# Arduino_Breakout.net
KiCad netlist of a schematic drawn in Altium Designer
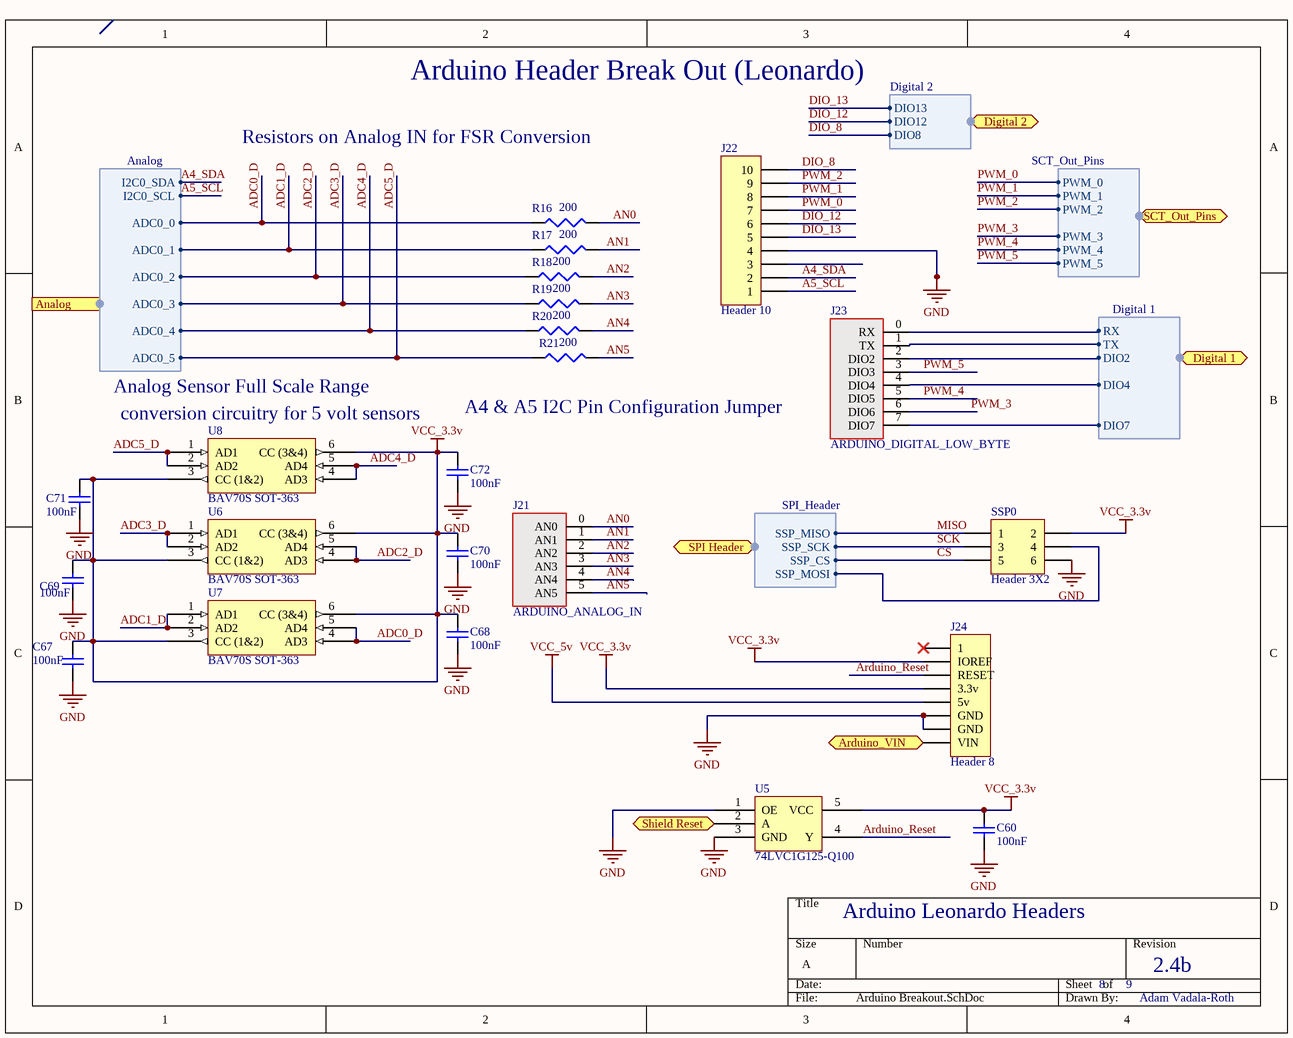
[diagram p0: Arduino Breakout.SchDoc]

(export (version "E")
  (design (tool "Eeschema 10.0.6"))
  (components
    (comp (ref "C60")
      (value "100nF")
      (footprint "1608[0603]")
      (description "Capacitor (Semiconductor SIM Model)")
      (fields (field (name "Comment") "Cap Semi") (field (name "PUBLISHER") "Altium Limited"))
      (libsource (lib "Miscellaneous Devices") (part "Cap Semi"))
    )
    (comp (ref "C67")
      (value "100nF")
      (footprint "1608[0603]")
      (description "Capacitor (Semiconductor SIM Model)")
      (fields (field (name "Comment") "Cap Semi") (field (name "PUBLISHER") "Altium Limited"))
      (libsource (lib "Miscellaneous Devices") (part "Cap Semi"))
    )
    (comp (ref "C68")
      (value "100nF")
      (footprint "1608[0603]")
      (description "Capacitor (Semiconductor SIM Model)")
      (fields (field (name "Comment") "Cap Semi") (field (name "PUBLISHER") "Altium Limited"))
      (libsource (lib "Miscellaneous Devices") (part "Cap Semi"))
    )
    (comp (ref "C69")
      (value "100nF")
      (footprint "1608[0603]")
      (description "Capacitor (Semiconductor SIM Model)")
      (fields (field (name "Comment") "Cap Semi") (field (name "PUBLISHER") "Altium Limited"))
      (libsource (lib "Miscellaneous Devices") (part "Cap Semi"))
    )
    (comp (ref "C70")
      (value "100nF")
      (footprint "1608[0603]")
      (description "Capacitor (Semiconductor SIM Model)")
      (fields (field (name "Comment") "Cap Semi") (field (name "PUBLISHER") "Altium Limited"))
      (libsource (lib "Miscellaneous Devices") (part "Cap Semi"))
    )
    (comp (ref "C71")
      (value "100nF")
      (footprint "1608[0603]")
      (description "Capacitor (Semiconductor SIM Model)")
      (fields (field (name "Comment") "Cap Semi") (field (name "PUBLISHER") "Altium Limited"))
      (libsource (lib "Miscellaneous Devices") (part "Cap Semi"))
    )
    (comp (ref "C72")
      (value "100nF")
      (footprint "1608[0603]")
      (description "Capacitor (Semiconductor SIM Model)")
      (fields (field (name "Comment") "Cap Semi") (field (name "PUBLISHER") "Altium Limited"))
      (libsource (lib "Miscellaneous Devices") (part "Cap Semi"))
    )
    (comp (ref "J21")
      (value "ARDUINO_ANALOG_IN")
      (footprint "HDR1X6")
      (description "6-pin socket")
      (libsource (lib "Rascal") (part "ARDUINO_ANALOG_IN"))
    )
    (comp (ref "J22")
      (value "Header 10")
      (footprint "HDR1X10")
      (description "Header, 10-Pin")
      (fields (field (name "PUBLISHER") "Altium Limited"))
      (libsource (lib "Miscellaneous Connectors") (part "Header 10"))
    )
    (comp (ref "J23")
      (value "ARDUINO_DIGITAL_LOW_BYTE")
      (footprint "HDR1X8")
      (description "8-pin socket")
      (libsource (lib "Rascal") (part "ARDUINO_DIGITAL_LOW_BYTE"))
    )
    (comp (ref "J24")
      (value "Header 8")
      (footprint "HDR1X8")
      (description "Header, 8-Pin")
      (fields (field (name "PUBLISHER") "Altium Limited"))
      (libsource (lib "Miscellaneous Connectors") (part "Header 8"))
    )
    (comp (ref "R16")
      (value "200")
      (footprint "J1-0603")
      (description "Resistor")
      (fields (field (name "Comment") "Res3") (field (name "PUBLISHER") "Altium Limited"))
      (libsource (lib "Miscellaneous Devices") (part "Res3"))
    )
    (comp (ref "R17")
      (value "200")
      (footprint "J1-0603")
      (description "Resistor")
      (fields (field (name "Comment") "Res3") (field (name "PUBLISHER") "Altium Limited"))
      (libsource (lib "Miscellaneous Devices") (part "Res3"))
    )
    (comp (ref "R18")
      (value "200")
      (footprint "J1-0603")
      (description "Resistor")
      (fields (field (name "Comment") "Res3") (field (name "PUBLISHER") "Altium Limited"))
      (libsource (lib "Miscellaneous Devices") (part "Res3"))
    )
    (comp (ref "R19")
      (value "200")
      (footprint "J1-0603")
      (description "Resistor")
      (fields (field (name "Comment") "Res3") (field (name "PUBLISHER") "Altium Limited"))
      (libsource (lib "Miscellaneous Devices") (part "Res3"))
    )
    (comp (ref "R20")
      (value "200")
      (footprint "J1-0603")
      (description "Resistor")
      (fields (field (name "Comment") "Res3") (field (name "PUBLISHER") "Altium Limited"))
      (libsource (lib "Miscellaneous Devices") (part "Res3"))
    )
    (comp (ref "R21")
      (value "200")
      (footprint "J1-0603")
      (description "Resistor")
      (fields (field (name "Comment") "Res3") (field (name "PUBLISHER") "Altium Limited"))
      (libsource (lib "Miscellaneous Devices") (part "Res3"))
    )
    (comp (ref "SSP0")
      (value "Header 3X2")
      (footprint "HDR2X3")
      (description "Header, 3-Pin, Dual row")
      (fields (field (name "PUBLISHER") "Altium Limited"))
      (libsource (lib "Miscellaneous Connectors") (part "Header 3X2"))
    )
    (comp (ref "U5")
      (value "74LVC1G125-Q100")
      (footprint "74LVC1G125-Q100")
      (libsource (lib "AHD Part Library") (part "74LVC1G125-Q100"))
    )
    (comp (ref "U6")
      (value "BAV70S SOT-363")
      (footprint "BAV70S_SOT363")
      (libsource (lib "AHD Part Library") (part "BAV70S SOT-363"))
    )
    (comp (ref "U7")
      (value "BAV70S SOT-363")
      (footprint "BAV70S_SOT363")
      (libsource (lib "AHD Part Library") (part "BAV70S SOT-363"))
    )
    (comp (ref "U8")
      (value "BAV70S SOT-363")
      (footprint "BAV70S_SOT363")
      (libsource (lib "AHD Part Library") (part "BAV70S SOT-363"))
    )
  )
  (nets
    (net (code "7") (name "/A4_SDA") (class "Default")
      (node (ref "J22") (pin "2") (pinfunction "2_2") (pintype "passive"))
    )
    (net (code "8") (name "/A5_SCL") (class "Default")
      (node (ref "J22") (pin "1") (pinfunction "1_1") (pintype "passive"))
    )
    (net (code "9") (name "/ADC0_D") (class "Default")
      (node (ref "R16") (pin "1") (pinfunction "1_1") (pintype "passive"))
      (node (ref "U7") (pin "4") (pinfunction "AD3_4") (pintype "input"))
      (node (ref "U7") (pin "5") (pinfunction "AD4_5") (pintype "input"))
    )
    (net (code "10") (name "/ADC1_D") (class "Default")
      (node (ref "R17") (pin "1") (pinfunction "1_1") (pintype "passive"))
      (node (ref "U7") (pin "1") (pinfunction "AD1_1") (pintype "input"))
      (node (ref "U7") (pin "2") (pinfunction "AD2_2") (pintype "input"))
    )
    (net (code "11") (name "/ADC2_D") (class "Default")
      (node (ref "R18") (pin "1") (pinfunction "1_1") (pintype "passive"))
      (node (ref "U6") (pin "4") (pinfunction "AD3_4") (pintype "input"))
      (node (ref "U6") (pin "5") (pinfunction "AD4_5") (pintype "input"))
    )
    (net (code "12") (name "/ADC3_D") (class "Default")
      (node (ref "R19") (pin "1") (pinfunction "1_1") (pintype "passive"))
      (node (ref "U6") (pin "1") (pinfunction "AD1_1") (pintype "input"))
      (node (ref "U6") (pin "2") (pinfunction "AD2_2") (pintype "input"))
    )
    (net (code "13") (name "/ADC4_D") (class "Default")
      (node (ref "R20") (pin "1") (pinfunction "1_1") (pintype "passive"))
      (node (ref "U8") (pin "4") (pinfunction "AD3_4") (pintype "input"))
      (node (ref "U8") (pin "5") (pinfunction "AD4_5") (pintype "input"))
    )
    (net (code "14") (name "/ADC5_D") (class "Default")
      (node (ref "R21") (pin "1") (pinfunction "1_1") (pintype "passive"))
      (node (ref "U8") (pin "1") (pinfunction "AD1_1") (pintype "input"))
      (node (ref "U8") (pin "2") (pinfunction "AD2_2") (pintype "input"))
    )
    (net (code "15") (name "/AN0") (class "Default")
      (node (ref "J21") (pin "0") (pinfunction "AN0_0") (pintype "passive"))
      (node (ref "R16") (pin "2") (pinfunction "2_2") (pintype "passive"))
    )
    (net (code "16") (name "/AN1") (class "Default")
      (node (ref "J21") (pin "1") (pinfunction "AN1_1") (pintype "passive"))
      (node (ref "R17") (pin "2") (pinfunction "2_2") (pintype "passive"))
    )
    (net (code "17") (name "/AN2") (class "Default")
      (node (ref "J21") (pin "2") (pinfunction "AN2_2") (pintype "passive"))
      (node (ref "R18") (pin "2") (pinfunction "2_2") (pintype "passive"))
    )
    (net (code "18") (name "/AN3") (class "Default")
      (node (ref "J21") (pin "3") (pinfunction "AN3_3") (pintype "passive"))
      (node (ref "R19") (pin "2") (pinfunction "2_2") (pintype "passive"))
    )
    (net (code "19") (name "/AN4") (class "Default")
      (node (ref "J21") (pin "4") (pinfunction "AN4_4") (pintype "passive"))
      (node (ref "R20") (pin "2") (pinfunction "2_2") (pintype "passive"))
    )
    (net (code "20") (name "/AN5") (class "Default")
      (node (ref "J21") (pin "5") (pinfunction "AN5_5") (pintype "passive"))
      (node (ref "R21") (pin "2") (pinfunction "2_2") (pintype "passive"))
    )
    (net (code "21") (name "/Arduino_Reset") (class "Default")
      (node (ref "J24") (pin "3") (pinfunction "RESET_3") (pintype "passive"))
      (node (ref "U5") (pin "4") (pinfunction "Y_4") (pintype "passive"))
    )
    (net (code "22") (name "/Arduino_VIN") (class "Default")
      (node (ref "J24") (pin "8") (pinfunction "VIN_8") (pintype "passive"))
    )
    (net (code "23") (name "/CS") (class "Default")
      (node (ref "SSP0") (pin "5") (pinfunction "5_5") (pintype "passive"))
    )
    (net (code "24") (name "/DIO2") (class "Default")
      (node (ref "J23") (pin "2") (pinfunction "DIO2_2") (pintype "passive"))
    )
    (net (code "25") (name "/DIO4") (class "Default")
      (node (ref "J23") (pin "4") (pinfunction "DIO4_4") (pintype "passive"))
    )
    (net (code "26") (name "/DIO7") (class "Default")
      (node (ref "J23") (pin "7") (pinfunction "DIO7_7") (pintype "passive"))
    )
    (net (code "27") (name "/DIO_8") (class "Default")
      (node (ref "J22") (pin "10") (pinfunction "10_10") (pintype "passive"))
    )
    (net (code "28") (name "/DIO_12") (class "Default")
      (node (ref "J22") (pin "6") (pinfunction "6_6") (pintype "passive"))
    )
    (net (code "29") (name "/DIO_13") (class "Default")
      (node (ref "J22") (pin "5") (pinfunction "5_5") (pintype "passive"))
    )
    (net (code "30") (name "/MISO") (class "Default")
      (node (ref "SSP0") (pin "1") (pinfunction "1_1") (pintype "passive"))
    )
    (net (code "31") (name "/PWM_0") (class "Default")
      (node (ref "J22") (pin "7") (pinfunction "7_7") (pintype "passive"))
    )
    (net (code "32") (name "/PWM_1") (class "Default")
      (node (ref "J22") (pin "8") (pinfunction "8_8") (pintype "passive"))
    )
    (net (code "33") (name "/PWM_2") (class "Default")
      (node (ref "J22") (pin "9") (pinfunction "9_9") (pintype "passive"))
    )
    (net (code "34") (name "/PWM_3") (class "Default")
      (node (ref "J23") (pin "6") (pinfunction "DIO6_6") (pintype "passive"))
    )
    (net (code "35") (name "/PWM_4") (class "Default")
      (node (ref "J23") (pin "5") (pinfunction "DIO5_5") (pintype "passive"))
    )
    (net (code "36") (name "/PWM_5") (class "Default")
      (node (ref "J23") (pin "3") (pinfunction "DIO3_3") (pintype "passive"))
    )
    (net (code "37") (name "/RX") (class "Default")
      (node (ref "J23") (pin "0") (pinfunction "RX_0") (pintype "passive"))
    )
    (net (code "38") (name "/SCK") (class "Default")
      (node (ref "SSP0") (pin "3") (pinfunction "3_3") (pintype "passive"))
    )
    (net (code "39") (name "/SSP_MOSI") (class "Default")
      (node (ref "SSP0") (pin "4") (pinfunction "4_4") (pintype "passive"))
    )
    (net (code "40") (name "/Shield Reset") (class "Default")
      (node (ref "U5") (pin "2") (pinfunction "A_2") (pintype "passive"))
    )
    (net (code "41") (name "/TX") (class "Default")
      (node (ref "J23") (pin "1") (pinfunction "TX_1") (pintype "passive"))
    )
    (net (code "47") (name "GND") (class "Default")
      (node (ref "C60") (pin "2") (pinfunction "2_2") (pintype "passive"))
      (node (ref "C67") (pin "2") (pinfunction "2_2") (pintype "passive"))
      (node (ref "C68") (pin "2") (pinfunction "2_2") (pintype "passive"))
      (node (ref "C69") (pin "2") (pinfunction "2_2") (pintype "passive"))
      (node (ref "C70") (pin "2") (pinfunction "2_2") (pintype "passive"))
      (node (ref "C71") (pin "2") (pinfunction "2_2") (pintype "passive"))
      (node (ref "C72") (pin "2") (pinfunction "2_2") (pintype "passive"))
      (node (ref "J22") (pin "4") (pinfunction "4_4") (pintype "passive"))
      (node (ref "J24") (pin "6") (pinfunction "GND_6") (pintype "passive"))
      (node (ref "J24") (pin "7") (pinfunction "GND_7") (pintype "passive"))
      (node (ref "SSP0") (pin "6") (pinfunction "6_6") (pintype "passive"))
      (node (ref "U5") (pin "1") (pinfunction "OE_1") (pintype "passive"))
      (node (ref "U5") (pin "3") (pinfunction "GND_3") (pintype "passive"))
    )
    (net (code "48") (name "VCC_3.3v") (class "Default")
      (node (ref "C60") (pin "1") (pinfunction "1_1") (pintype "passive"))
      (node (ref "C67") (pin "1") (pinfunction "1_1") (pintype "passive"))
      (node (ref "C68") (pin "1") (pinfunction "1_1") (pintype "passive"))
      (node (ref "C69") (pin "1") (pinfunction "1_1") (pintype "passive"))
      (node (ref "C70") (pin "1") (pinfunction "1_1") (pintype "passive"))
      (node (ref "C71") (pin "1") (pinfunction "1_1") (pintype "passive"))
      (node (ref "C72") (pin "1") (pinfunction "1_1") (pintype "passive"))
      (node (ref "J24") (pin "2") (pinfunction "IOREF_2") (pintype "passive"))
      (node (ref "J24") (pin "4") (pinfunction "3.3v_4") (pintype "passive"))
      (node (ref "SSP0") (pin "2") (pinfunction "2_2") (pintype "passive"))
      (node (ref "U5") (pin "5") (pinfunction "VCC_5") (pintype "passive"))
      (node (ref "U6") (pin "3") (pinfunction "CC_(1&2)_3") (pintype "output"))
      (node (ref "U6") (pin "6") (pinfunction "CC_(3&4)_6") (pintype "output"))
      (node (ref "U7") (pin "3") (pinfunction "CC_(1&2)_3") (pintype "output"))
      (node (ref "U7") (pin "6") (pinfunction "CC_(3&4)_6") (pintype "output"))
      (node (ref "U8") (pin "3") (pinfunction "CC_(1&2)_3") (pintype "output"))
      (node (ref "U8") (pin "6") (pinfunction "CC_(3&4)_6") (pintype "output"))
    )
    (net (code "49") (name "VCC_5v") (class "Default")
      (node (ref "J24") (pin "5") (pinfunction "5v_5") (pintype "passive"))
    )
    (net (code "50") (name "unconnected-(J22-Pad3)") (class "Default")
      (node (ref "J22") (pin "3") (pinfunction "3_3") (pintype "passive"))
    )
    (net (code "51") (name "unconnected-(J24-Pad1)") (class "Default")
      (node (ref "J24") (pin "1") (pinfunction "1_1") (pintype "passive+no_connect"))
    )
  )
)
